# Main.net
KiCad netlist of a schematic drawn in Altium Designer
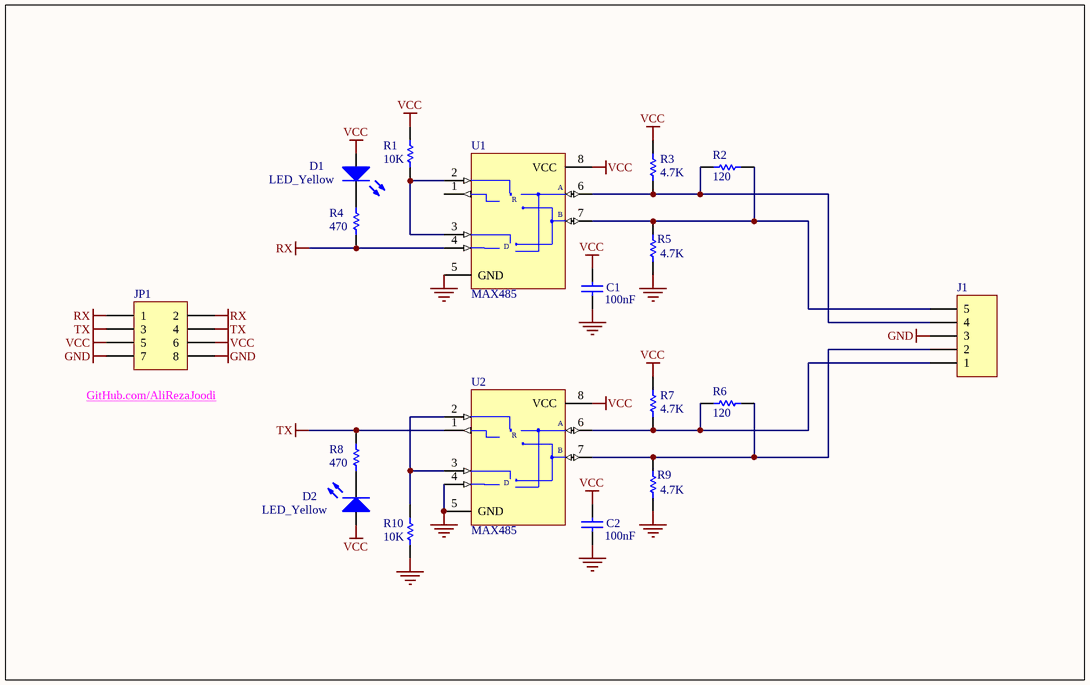
[diagram p0: Main.SchDoc]

(export (version "E")
  (design (tool "Eeschema 10.0.6"))
  (components
    (comp (ref "C1")
      (value "100nF")
      (footprint "RAD0.1")
      (description "Capacitor")
      (fields (field (name "MANUFACTURER") "Generic Components") (field (name "PUBLISHER") "Altium Limited"))
      (libsource (lib "Miscellaneous Devices") (part "Cap"))
    )
    (comp (ref "C2")
      (value "100nF")
      (footprint "RAD0.1")
      (description "Capacitor")
      (fields (field (name "MANUFACTURER") "Generic Components") (field (name "PUBLISHER") "Altium Limited"))
      (libsource (lib "Miscellaneous Devices") (part "Cap"))
    )
    (comp (ref "D1")
      (value "LED_Yellow")
      (footprint "LED-5mm_Red")
      (description "Typical INFRARED GaAs LED")
      (fields (field (name "MANUFACTURER") "Generic Components") (field (name "PUBLISHER") "Altium Limited"))
      (libsource (lib "Miscellaneous Devices") (part "LED"))
    )
    (comp (ref "D2")
      (value "LED_Yellow")
      (footprint "LED-5mm_Red")
      (description "Typical INFRARED GaAs LED")
      (fields (field (name "MANUFACTURER") "Generic Components") (field (name "PUBLISHER") "Altium Limited"))
      (libsource (lib "Miscellaneous Devices") (part "LED"))
    )
    (comp (ref "J1")
      (value "Header 5")
      (footprint "Fonics_5PIN_1")
      (description "Header, 5-Pin")
      (fields (field (name "PUBLISHER") "Altium Limited"))
      (libsource (lib "Miscellaneous Connectors") (part "Header 5"))
    )
    (comp (ref "JP1")
      (value "Header 4X2H")
      (footprint "HDR2X4H")
      (description "Header, 4-Pin, Dual row,  Right Angle")
      (fields (field (name "MANUFACTURER") "Generic Components") (field (name "PUBLISHER") "Altium Limited"))
      (libsource (lib "Miscellaneous Connectors") (part "Header 4X2H"))
    )
    (comp (ref "R1")
      (value "10K")
      (footprint "AXIAL-0.4")
      (description "Resistor")
      (fields (field (name "PUBLISHER") "Altium Limited"))
      (libsource (lib "Miscellaneous Devices") (part "Res1"))
    )
    (comp (ref "R2")
      (value "120")
      (footprint "AXIAL-0.4")
      (description "Resistor")
      (fields (field (name "PUBLISHER") "Altium Limited"))
      (libsource (lib "Miscellaneous Devices") (part "Res1"))
    )
    (comp (ref "R3")
      (value "4.7K")
      (footprint "AXIAL-0.4")
      (description "Resistor")
      (fields (field (name "PUBLISHER") "Altium Limited"))
      (libsource (lib "Miscellaneous Devices") (part "Res1"))
    )
    (comp (ref "R4")
      (value "470")
      (footprint "AXIAL-0.4")
      (description "Resistor")
      (fields (field (name "PUBLISHER") "Altium Limited"))
      (libsource (lib "Miscellaneous Devices") (part "Res1"))
    )
    (comp (ref "R5")
      (value "4.7K")
      (footprint "AXIAL-0.4")
      (description "Resistor")
      (fields (field (name "PUBLISHER") "Altium Limited"))
      (libsource (lib "Miscellaneous Devices") (part "Res1"))
    )
    (comp (ref "R6")
      (value "120")
      (footprint "AXIAL-0.4")
      (description "Resistor")
      (fields (field (name "PUBLISHER") "Altium Limited"))
      (libsource (lib "Miscellaneous Devices") (part "Res1"))
    )
    (comp (ref "R7")
      (value "4.7K")
      (footprint "AXIAL-0.4")
      (description "Resistor")
      (fields (field (name "PUBLISHER") "Altium Limited"))
      (libsource (lib "Miscellaneous Devices") (part "Res1"))
    )
    (comp (ref "R8")
      (value "470")
      (footprint "AXIAL-0.4")
      (description "Resistor")
      (fields (field (name "PUBLISHER") "Altium Limited"))
      (libsource (lib "Miscellaneous Devices") (part "Res1"))
    )
    (comp (ref "R9")
      (value "4.7K")
      (footprint "AXIAL-0.4")
      (description "Resistor")
      (fields (field (name "PUBLISHER") "Altium Limited"))
      (libsource (lib "Miscellaneous Devices") (part "Res1"))
    )
    (comp (ref "R10")
      (value "10K")
      (footprint "AXIAL-0.4")
      (description "Resistor")
      (fields (field (name "PUBLISHER") "Altium Limited"))
      (libsource (lib "Miscellaneous Devices") (part "Res1"))
    )
    (comp (ref "U1")
      (value "MAX485")
      (footprint "PA8")
      (description "Low-Power, Slew-Rate-Limited RS-485/RS-422 Transceiver")
      (fields (field (name "PUBLISHER") "Altium Limited"))
      (libsource (lib "Maxim Communication Transceiver") (part "MAX485CPA"))
    )
    (comp (ref "U2")
      (value "MAX485")
      (footprint "PA8")
      (description "Low-Power, Slew-Rate-Limited RS-485/RS-422 Transceiver")
      (fields (field (name "PUBLISHER") "Altium Limited"))
      (libsource (lib "Maxim Communication Transceiver") (part "MAX485CPA"))
    )
  )
  (nets
    (net (code "1") (name "GND") (class "Default")
      (node (ref "C1") (pin "1") (pinfunction "1_1") (pintype "passive"))
      (node (ref "C2") (pin "1") (pinfunction "1_1") (pintype "passive"))
      (node (ref "J1") (pin "3") (pinfunction "3_3") (pintype "passive"))
      (node (ref "JP1") (pin "7") (pinfunction "7_7") (pintype "passive"))
      (node (ref "JP1") (pin "8") (pinfunction "8_8") (pintype "passive"))
      (node (ref "R10") (pin "1") (pinfunction "1_1") (pintype "passive"))
      (node (ref "R5") (pin "2") (pinfunction "2_2") (pintype "passive"))
      (node (ref "R9") (pin "2") (pinfunction "2_2") (pintype "passive"))
      (node (ref "U1") (pin "5") (pinfunction "GND_5") (pintype "power_in"))
      (node (ref "U2") (pin "4") (pinfunction "DI_4") (pintype "input"))
      (node (ref "U2") (pin "5") (pinfunction "GND_5") (pintype "power_in"))
    )
    (net (code "2") (name "Net-(D1-K)") (class "Default")
      (node (ref "D1") (pin "2") (pinfunction "K_2") (pintype "passive"))
      (node (ref "R4") (pin "2") (pinfunction "2_2") (pintype "passive"))
    )
    (net (code "3") (name "Net-(D2-K)") (class "Default")
      (node (ref "D2") (pin "2") (pinfunction "K_2") (pintype "passive"))
      (node (ref "R8") (pin "2") (pinfunction "2_2") (pintype "passive"))
    )
    (net (code "4") (name "Net-(U1-A)") (class "Default")
      (node (ref "J1") (pin "4") (pinfunction "4_4") (pintype "passive"))
      (node (ref "R2") (pin "1") (pinfunction "1_1") (pintype "passive"))
      (node (ref "R3") (pin "2") (pinfunction "2_2") (pintype "passive"))
      (node (ref "U1") (pin "6") (pinfunction "A_6") (pintype "bidirectional"))
    )
    (net (code "5") (name "Net-(U1-B)") (class "Default")
      (node (ref "J1") (pin "5") (pinfunction "5_5") (pintype "passive"))
      (node (ref "R2") (pin "2") (pinfunction "2_2") (pintype "passive"))
      (node (ref "R5") (pin "1") (pinfunction "1_1") (pintype "passive"))
      (node (ref "U1") (pin "7") (pinfunction "B_7") (pintype "bidirectional"))
    )
    (net (code "6") (name "Net-(U1-DE)") (class "Default")
      (node (ref "R1") (pin "1") (pinfunction "1_1") (pintype "passive"))
      (node (ref "U1") (pin "2") (pinfunction "~{RE}_2") (pintype "input"))
      (node (ref "U1") (pin "3") (pinfunction "DE_3") (pintype "input"))
    )
    (net (code "7") (name "Net-(U2-A)") (class "Default")
      (node (ref "J1") (pin "1") (pinfunction "1_1") (pintype "passive"))
      (node (ref "R6") (pin "1") (pinfunction "1_1") (pintype "passive"))
      (node (ref "R7") (pin "2") (pinfunction "2_2") (pintype "passive"))
      (node (ref "U2") (pin "6") (pinfunction "A_6") (pintype "bidirectional"))
    )
    (net (code "8") (name "Net-(U2-B)") (class "Default")
      (node (ref "J1") (pin "2") (pinfunction "2_2") (pintype "passive"))
      (node (ref "R6") (pin "2") (pinfunction "2_2") (pintype "passive"))
      (node (ref "R9") (pin "1") (pinfunction "1_1") (pintype "passive"))
      (node (ref "U2") (pin "7") (pinfunction "B_7") (pintype "bidirectional"))
    )
    (net (code "9") (name "Net-(U2-DE)") (class "Default")
      (node (ref "R10") (pin "2") (pinfunction "2_2") (pintype "passive"))
      (node (ref "U2") (pin "2") (pinfunction "~{RE}_2") (pintype "input"))
      (node (ref "U2") (pin "3") (pinfunction "DE_3") (pintype "input"))
    )
    (net (code "10") (name "RX") (class "Default")
      (node (ref "JP1") (pin "1") (pinfunction "1_1") (pintype "passive"))
      (node (ref "JP1") (pin "2") (pinfunction "2_2") (pintype "passive"))
      (node (ref "R4") (pin "1") (pinfunction "1_1") (pintype "passive"))
      (node (ref "U1") (pin "4") (pinfunction "DI_4") (pintype "input"))
    )
    (net (code "11") (name "TX") (class "Default")
      (node (ref "JP1") (pin "3") (pinfunction "3_3") (pintype "passive"))
      (node (ref "JP1") (pin "4") (pinfunction "4_4") (pintype "passive"))
      (node (ref "R8") (pin "1") (pinfunction "1_1") (pintype "passive"))
      (node (ref "U2") (pin "1") (pinfunction "RO_1") (pintype "output"))
    )
    (net (code "12") (name "VCC") (class "Default")
      (node (ref "C1") (pin "2") (pinfunction "2_2") (pintype "passive"))
      (node (ref "C2") (pin "2") (pinfunction "2_2") (pintype "passive"))
      (node (ref "D1") (pin "1") (pinfunction "A_1") (pintype "passive"))
      (node (ref "D2") (pin "1") (pinfunction "A_1") (pintype "passive"))
      (node (ref "JP1") (pin "5") (pinfunction "5_5") (pintype "passive"))
      (node (ref "JP1") (pin "6") (pinfunction "6_6") (pintype "passive"))
      (node (ref "R1") (pin "2") (pinfunction "2_2") (pintype "passive"))
      (node (ref "R3") (pin "1") (pinfunction "1_1") (pintype "passive"))
      (node (ref "R7") (pin "1") (pinfunction "1_1") (pintype "passive"))
      (node (ref "U1") (pin "8") (pinfunction "VCC_8") (pintype "power_in"))
      (node (ref "U2") (pin "8") (pinfunction "VCC_8") (pintype "power_in"))
    )
    (net (code "13") (name "unconnected-(U1-RO-Pad1)") (class "Default")
      (node (ref "U1") (pin "1") (pinfunction "RO_1") (pintype "output"))
    )
  )
)
